# Kube-Module-PS.net
KiCad netlist of a schematic drawn in EAGLE
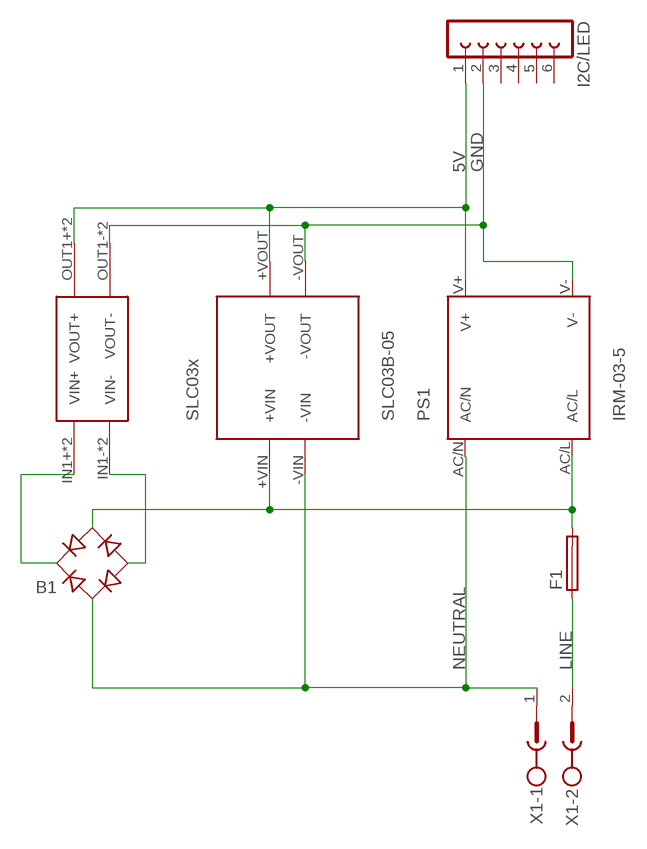
[diagram p0: schematic, sheet 1]

(export (version "E")
  (design (tool "Eeschema 10.0.6"))
  (components
    (comp (ref "B1")
      (value "RB1A")
      (footprint "eagle-import:RB1A")
      (libsource (lib "eagle-import") (part "RB1A"))
    )
    (comp (ref "F1")
      (value "LITTLEFUSE")
      (footprint "eagle-import:LITTLEFUSE")
      (libsource (lib "eagle-import") (part "LITTLEFUSE"))
    )
    (comp (ref "I2C/LED")
      (value "FE06-1")
      (footprint "eagle-import:FE06")
      (libsource (lib "eagle-import") (part "FE06-1"))
    )
    (comp (ref "MP1584")
      (value "MP1584")
      (footprint "eagle-import:DC-BRICK")
      (libsource (lib "eagle-import") (part "MP1584"))
    )
    (comp (ref "PS1")
      (value "IRM-03-5")
      (footprint "eagle-import:IRM_03")
      (libsource (lib "eagle-import") (part "IRM_03IRM_03"))
    )
    (comp (ref "SLC03X")
      (value "SLC03B-05")
      (footprint "eagle-import:SLC03X")
      (libsource (lib "eagle-import") (part "SLC03XSLC03X"))
    )
    (comp (ref "X1")
      (value "MSTBV2")
      (footprint "eagle-import:MSTBV2")
      (libsource (lib "eagle-import") (part "MSTBV2"))
    )
  )
  (nets
    (net (code "1") (name "/5V") (class "Default")
      (node (ref "I2C/LED") (pin "1") (pinfunction "1_1") (pintype "passive"))
      (node (ref "MP1584") (pin "OUT1+") (pinfunction "VOUT+_OUT1+") (pintype "output"))
      (node (ref "MP1584") (pin "OUT2+") (pinfunction "VOUT+_OUT2+") (pintype "output"))
      (node (ref "PS1") (pin "V+") (pinfunction "V+_V+") (pintype "output"))
      (node (ref "SLC03X") (pin "+VOUT") (pinfunction "+VOUT_+VOUT") (pintype "output"))
    )
    (net (code "2") (name "/GND") (class "Default")
      (node (ref "I2C/LED") (pin "2") (pinfunction "2_2") (pintype "passive"))
      (node (ref "MP1584") (pin "OUT1-") (pinfunction "VOUT-_OUT1-") (pintype "output"))
      (node (ref "MP1584") (pin "OUT2-") (pinfunction "VOUT-_OUT2-") (pintype "output"))
      (node (ref "PS1") (pin "V-") (pinfunction "V-_V-") (pintype "output"))
      (node (ref "SLC03X") (pin "-VOUT") (pinfunction "-VOUT_-VOUT") (pintype "output"))
    )
    (net (code "3") (name "/LINE") (class "Default")
      (node (ref "F1") (pin "1") (pinfunction "1_1") (pintype "passive"))
      (node (ref "X1") (pin "2") (pinfunction "SK_2") (pintype "passive"))
    )
    (net (code "4") (name "/NEUTRAL") (class "Default")
      (node (ref "B1") (pin "AC1") (pinfunction "AC1_AC1") (pintype "passive"))
      (node (ref "PS1") (pin "AC/N") (pinfunction "AC/N_AC/N") (pintype "input"))
      (node (ref "SLC03X") (pin "-VIN") (pinfunction "-VIN_-VIN") (pintype "input"))
      (node (ref "X1") (pin "1") (pinfunction "SK_1") (pintype "passive"))
    )
    (net (code "5") (name "Net-(B1-Pad+)") (class "Default")
      (node (ref "B1") (pin "+") (pinfunction "+_+") (pintype "passive"))
      (node (ref "MP1584") (pin "IN1+") (pinfunction "VIN+_IN1+") (pintype "input"))
      (node (ref "MP1584") (pin "IN2+") (pinfunction "VIN+_IN2+") (pintype "input"))
    )
    (net (code "6") (name "Net-(B1-Pad-)") (class "Default")
      (node (ref "B1") (pin "-") (pinfunction "-_-") (pintype "passive"))
      (node (ref "MP1584") (pin "IN1-") (pinfunction "VIN-_IN1-") (pintype "input"))
      (node (ref "MP1584") (pin "IN2-") (pinfunction "VIN-_IN2-") (pintype "input"))
    )
    (net (code "7") (name "Net-(B1-PadAC2)") (class "Default")
      (node (ref "B1") (pin "AC2") (pinfunction "AC2_AC2") (pintype "passive"))
      (node (ref "F1") (pin "2") (pinfunction "2_2") (pintype "passive"))
      (node (ref "PS1") (pin "AC/L") (pinfunction "AC/L_AC/L") (pintype "input"))
      (node (ref "SLC03X") (pin "+VIN") (pinfunction "+VIN_+VIN") (pintype "input"))
    )
    (net (code "8") (name "unconnected-(I2C/LED-Pad3)") (class "Default")
      (node (ref "I2C/LED") (pin "3") (pinfunction "3_3") (pintype "passive"))
    )
    (net (code "9") (name "unconnected-(I2C/LED-Pad4)") (class "Default")
      (node (ref "I2C/LED") (pin "4") (pinfunction "4_4") (pintype "passive"))
    )
    (net (code "10") (name "unconnected-(I2C/LED-Pad5)") (class "Default")
      (node (ref "I2C/LED") (pin "5") (pinfunction "5_5") (pintype "passive"))
    )
    (net (code "11") (name "unconnected-(I2C/LED-Pad6)") (class "Default")
      (node (ref "I2C/LED") (pin "6") (pinfunction "6_6") (pintype "passive"))
    )
  )
)
